# LabDuinoBt.net
KiCad netlist of a schematic drawn in EAGLE
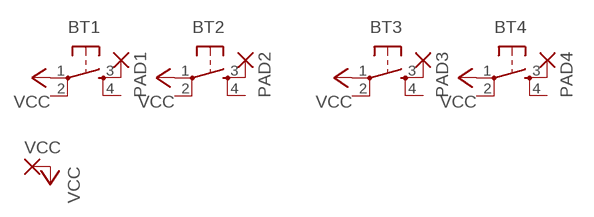
[diagram p0: schematic, sheet 1]

(export (version "E")
  (design (tool "Eeschema 10.0.6"))
  (components
    (comp (ref "BT1")
      (value "TAC_SWITCHPTH")
      (footprint "eagle-import:TACTILE-PTH")
      (libsource (lib "eagle-import") (part "TAC_SWITCHPTH"))
    )
    (comp (ref "BT2")
      (value "TAC_SWITCHPTH")
      (footprint "eagle-import:TACTILE-PTH")
      (libsource (lib "eagle-import") (part "TAC_SWITCHPTH"))
    )
    (comp (ref "BT3")
      (value "TAC_SWITCHPTH")
      (footprint "eagle-import:TACTILE-PTH")
      (libsource (lib "eagle-import") (part "TAC_SWITCHPTH"))
    )
    (comp (ref "BT4")
      (value "TAC_SWITCHPTH")
      (footprint "eagle-import:TACTILE-PTH")
      (libsource (lib "eagle-import") (part "TAC_SWITCHPTH"))
    )
    (comp (ref "PAD1")
      (value "1,6/0,9")
      (footprint "eagle-import:1,6_0,9")
      (libsource (lib "eagle-import") (part "1,6/0,9"))
    )
    (comp (ref "PAD2")
      (value "1,6/0,9")
      (footprint "eagle-import:1,6_0,9")
      (libsource (lib "eagle-import") (part "1,6/0,9"))
    )
    (comp (ref "PAD3")
      (value "1,6/0,9")
      (footprint "eagle-import:1,6_0,9")
      (libsource (lib "eagle-import") (part "1,6/0,9"))
    )
    (comp (ref "PAD4")
      (value "1,6/0,9")
      (footprint "eagle-import:1,6_0,9")
      (libsource (lib "eagle-import") (part "1,6/0,9"))
    )
    (comp (ref "VCC")
      (value "1,6/0,9")
      (footprint "eagle-import:1,6_0,9")
      (libsource (lib "eagle-import") (part "1,6/0,9"))
    )
  )
  (nets
    (net (code "1") (name "Net-(PAD1-P)") (class "Default")
      (node (ref "BT1") (pin "3") (pinfunction "3_3") (pintype "passive"))
      (node (ref "PAD1") (pin "1") (pinfunction "P_1") (pintype "passive"))
    )
    (net (code "2") (name "Net-(PAD2-P)") (class "Default")
      (node (ref "BT2") (pin "3") (pinfunction "3_3") (pintype "passive"))
      (node (ref "PAD2") (pin "1") (pinfunction "P_1") (pintype "passive"))
    )
    (net (code "3") (name "Net-(PAD3-P)") (class "Default")
      (node (ref "BT3") (pin "3") (pinfunction "3_3") (pintype "passive"))
      (node (ref "PAD3") (pin "1") (pinfunction "P_1") (pintype "passive"))
    )
    (net (code "4") (name "Net-(PAD4-P)") (class "Default")
      (node (ref "BT4") (pin "3") (pinfunction "3_3") (pintype "passive"))
      (node (ref "PAD4") (pin "1") (pinfunction "P_1") (pintype "passive"))
    )
    (net (code "5") (name "VCC") (class "Default")
      (node (ref "BT1") (pin "1") (pinfunction "1_1") (pintype "passive"))
      (node (ref "BT2") (pin "1") (pinfunction "1_1") (pintype "passive"))
      (node (ref "BT3") (pin "1") (pinfunction "1_1") (pintype "passive"))
      (node (ref "BT4") (pin "1") (pinfunction "1_1") (pintype "passive"))
      (node (ref "VCC") (pin "1") (pinfunction "P_1") (pintype "passive"))
    )
    (net (code "6") (name "unconnected-(BT1-Pad2)") (class "Default")
      (node (ref "BT1") (pin "2") (pinfunction "2_2") (pintype "passive"))
    )
    (net (code "7") (name "unconnected-(BT1-Pad4)") (class "Default")
      (node (ref "BT1") (pin "4") (pinfunction "4_4") (pintype "passive"))
    )
    (net (code "8") (name "unconnected-(BT2-Pad2)") (class "Default")
      (node (ref "BT2") (pin "2") (pinfunction "2_2") (pintype "passive"))
    )
    (net (code "9") (name "unconnected-(BT2-Pad4)") (class "Default")
      (node (ref "BT2") (pin "4") (pinfunction "4_4") (pintype "passive"))
    )
    (net (code "10") (name "unconnected-(BT3-Pad2)") (class "Default")
      (node (ref "BT3") (pin "2") (pinfunction "2_2") (pintype "passive"))
    )
    (net (code "11") (name "unconnected-(BT3-Pad4)") (class "Default")
      (node (ref "BT3") (pin "4") (pinfunction "4_4") (pintype "passive"))
    )
    (net (code "12") (name "unconnected-(BT4-Pad2)") (class "Default")
      (node (ref "BT4") (pin "2") (pinfunction "2_2") (pintype "passive"))
    )
    (net (code "13") (name "unconnected-(BT4-Pad4)") (class "Default")
      (node (ref "BT4") (pin "4") (pinfunction "4_4") (pintype "passive"))
    )
  )
)
